# COMMUNICATION.net
KiCad netlist of a schematic drawn in Altium Designer
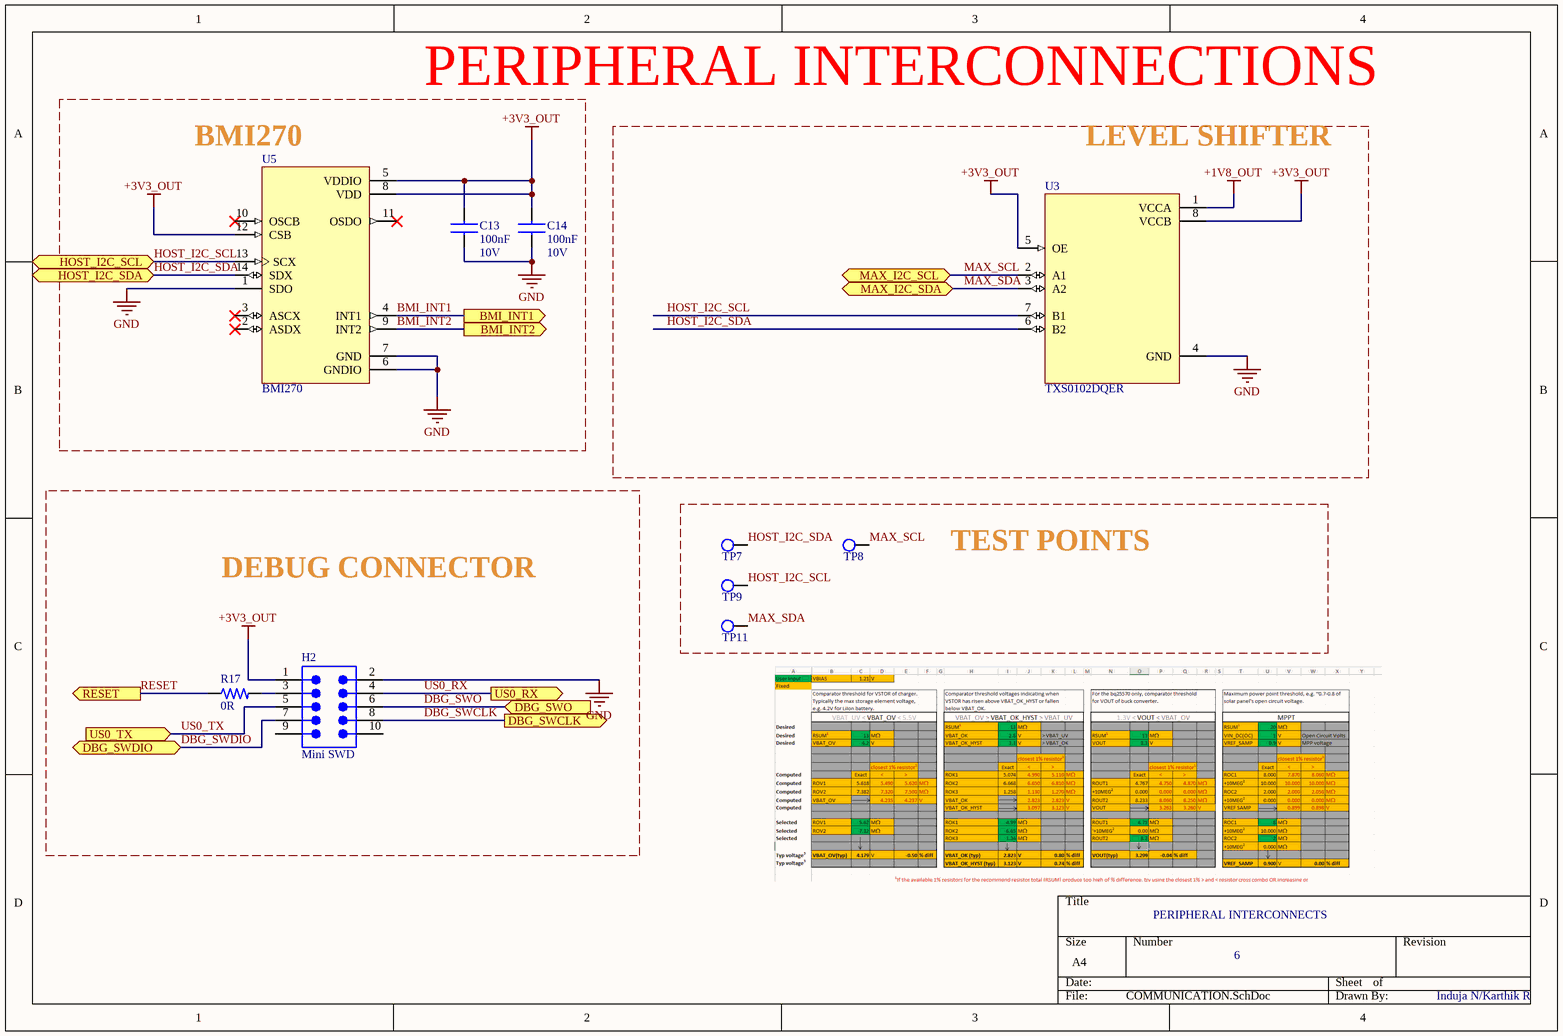
[diagram p0: COMMUNICATION.SchDoc]

(export (version "E")
  (design (tool "Eeschema 10.0.6"))
  (components
    (comp (ref "C13")
      (value "100nF")
      (footprint "CAP_0603_1MM")
      (description "0603 0.1 uF 10 V ±10% Tolerance X7R SMT Multilayer Ceramic Chip Capacitor")
      (fields
        (field (name "MANUFACTURER") "Vishay")
        (field (name "MANUFACTURER PART NUMBER") "VJ0603Y104KXQCW1BC")
        (field (name "VOLTAGE RATING (DC)") "10V")
      )
      (libsource (lib "LPEDT_Components") (part "CAP 0.1uF 0603"))
    )
    (comp (ref "C14")
      (value "100nF")
      (footprint "CAP_0603_1MM")
      (description "0603 0.1 uF 10 V ±10% Tolerance X7R SMT Multilayer Ceramic Chip Capacitor")
      (fields
        (field (name "MANUFACTURER") "Vishay")
        (field (name "MANUFACTURER PART NUMBER") "VJ0603Y104KXQCW1BC")
        (field (name "VOLTAGE RATING (DC)") "10V")
      )
      (libsource (lib "LPEDT_Components") (part "CAP 0.1uF 0603"))
    )
    (comp (ref "H2")
      (value "Mini SWD")
      (footprint "FTSH-105-01-XXX-DV-K")
      (description "Mini SWD 0.05\" Pitch Connector - 10 Pin SMT Box Header")
      (fields
        (field (name "MANUFACTURER") "Adafruit Industries")
        (field (name "MANUFACTURER PART NUMBER") "4048")
      )
      (libsource (lib "LPEDT_Components") (part "Debug Connector Mini SWD - 0.05{dblquote}"))
    )
    (comp (ref "R17")
      (value "0R")
      (footprint "RES_0603_1608X06")
      (description "GENERAL PURPOSE CHIP RESISTOR Metal Glaze/thick Film, 0.1W, 0ohm, Surface Mount, 0603")
      (fields
        (field (name "MANUFACTURER") "Yageo Group")
        (field (name "MANUFACTURER PART NUMBER") "RC0603JR-070RL")
      )
      (libsource (lib "LPEDT_Components") (part "RES 0R 0603"))
    )
    (comp (ref "TP7")
      (value "Test Point")
      (footprint "Test Point")
      (libsource (lib "LPEDT_Components") (part "Test Point"))
    )
    (comp (ref "TP8")
      (value "Test Point")
      (footprint "Test Point")
      (libsource (lib "LPEDT_Components") (part "Test Point"))
    )
    (comp (ref "TP9")
      (value "Test Point")
      (footprint "Test Point")
      (libsource (lib "LPEDT_Components") (part "Test Point"))
    )
    (comp (ref "TP11")
      (value "Test Point")
      (footprint "Test Point")
      (libsource (lib "LPEDT_Components") (part "Test Point"))
    )
    (comp (ref "U3")
      (value "TXS0102DQER")
      (footprint "SON35P140X100X40-8N")
      (description "2-Bit Bidirectional Voltage-Level Shifter for Open-Drain and Push-Pull Application")
      (fields (field (name "MF") "Texas Instruments"))
      (libsource (lib "LPEDT_Components") (part "TXS0102DQER"))
    )
    (comp (ref "U5")
      (value "BMI270")
      (footprint "XDCR_BMI270")
      (description "Accelerometer, Gyroscope, 6 Axis Sensor IÂ²C, SPI Output")
      (fields (field (name "DIGI-KEY_PART_NUMBER") "828-1091-2-ND") (field (name "MF") "Bosch Sensortec"))
      (libsource (lib "LPEDT_Components") (part "BMI270"))
    )
  )
  (nets
    (net (code "1") (name "+1V8_OUT") (class "Default")
      (node (ref "U3") (pin "1") (pinfunction "VCCA_1") (pintype "power_in"))
    )
    (net (code "2") (name "+3V3_OUT") (class "Default")
      (node (ref "C13") (pin "1") (pinfunction "1_1") (pintype "passive"))
      (node (ref "C14") (pin "1") (pinfunction "1_1") (pintype "passive"))
      (node (ref "H2") (pin "1") (pinfunction "1_1") (pintype "passive"))
      (node (ref "U3") (pin "5") (pinfunction "OE_5") (pintype "input"))
      (node (ref "U3") (pin "8") (pinfunction "VCCB_8") (pintype "power_in"))
      (node (ref "U5") (pin "12") (pinfunction "CSB_12") (pintype "input"))
      (node (ref "U5") (pin "5") (pinfunction "VDDIO_5") (pintype "power_in"))
      (node (ref "U5") (pin "8") (pinfunction "VDD_8") (pintype "power_in"))
    )
    (net (code "3") (name "/BMI_INT1") (class "Default")
      (node (ref "U5") (pin "4") (pinfunction "INT1_4") (pintype "output"))
    )
    (net (code "4") (name "/BMI_INT2") (class "Default")
      (node (ref "U5") (pin "9") (pinfunction "INT2_9") (pintype "output"))
    )
    (net (code "5") (name "/DBG_SWCLK") (class "Default")
      (node (ref "H2") (pin "8") (pinfunction "8_8") (pintype "passive"))
    )
    (net (code "6") (name "/DBG_SWDIO") (class "Default")
      (node (ref "H2") (pin "7") (pinfunction "7_7") (pintype "passive"))
    )
    (net (code "7") (name "/DBG_SWO") (class "Default")
      (node (ref "H2") (pin "6") (pinfunction "6_6") (pintype "passive"))
    )
    (net (code "8") (name "/HOST_I2C_SCL") (class "Default")
      (node (ref "TP9") (pin "1") (pinfunction "1_1") (pintype "passive"))
      (node (ref "U3") (pin "7") (pinfunction "B1_7") (pintype "bidirectional"))
      (node (ref "U5") (pin "13") (pinfunction "SCX_13") (pintype "input"))
    )
    (net (code "9") (name "/HOST_I2C_SDA") (class "Default")
      (node (ref "TP7") (pin "1") (pinfunction "1_1") (pintype "passive"))
      (node (ref "U3") (pin "6") (pinfunction "B2_6") (pintype "bidirectional"))
      (node (ref "U5") (pin "14") (pinfunction "SDX_14") (pintype "bidirectional"))
    )
    (net (code "10") (name "/MAX_SCL") (class "Default")
      (node (ref "TP8") (pin "1") (pinfunction "1_1") (pintype "passive"))
      (node (ref "U3") (pin "2") (pinfunction "A1_2") (pintype "bidirectional"))
    )
    (net (code "11") (name "/MAX_SDA") (class "Default")
      (node (ref "TP11") (pin "1") (pinfunction "1_1") (pintype "passive"))
      (node (ref "U3") (pin "3") (pinfunction "A2_3") (pintype "bidirectional"))
    )
    (net (code "12") (name "/RESET") (class "Default")
      (node (ref "R17") (pin "1") (pinfunction "1_1") (pintype "passive"))
    )
    (net (code "13") (name "/US0_RX") (class "Default")
      (node (ref "H2") (pin "4") (pinfunction "4_4") (pintype "passive"))
    )
    (net (code "14") (name "/US0_TX") (class "Default")
      (node (ref "H2") (pin "5") (pinfunction "5_5") (pintype "passive"))
    )
    (net (code "15") (name "GND") (class "Default")
      (node (ref "C13") (pin "2") (pinfunction "2_2") (pintype "passive"))
      (node (ref "C14") (pin "2") (pinfunction "2_2") (pintype "passive"))
      (node (ref "H2") (pin "2") (pinfunction "2_2") (pintype "passive"))
      (node (ref "U3") (pin "4") (pinfunction "GND_4") (pintype "power_in"))
      (node (ref "U5") (pin "1") (pinfunction "SDO_1") (pintype "passive"))
      (node (ref "U5") (pin "6") (pinfunction "GNDIO_6") (pintype "power_in"))
      (node (ref "U5") (pin "7") (pinfunction "GND_7") (pintype "power_in"))
    )
    (net (code "16") (name "Net-(H2-Pad3)") (class "Default")
      (node (ref "H2") (pin "3") (pinfunction "3_3") (pintype "passive"))
      (node (ref "R17") (pin "2") (pinfunction "2_2") (pintype "passive"))
    )
    (net (code "17") (name "unconnected-(H2-Pad9)") (class "Default")
      (node (ref "H2") (pin "9") (pinfunction "9_9") (pintype "passive"))
    )
    (net (code "18") (name "unconnected-(H2-Pad10)") (class "Default")
      (node (ref "H2") (pin "10") (pinfunction "10_10") (pintype "passive"))
    )
    (net (code "19") (name "unconnected-(U5-ASCX-Pad3)") (class "Default")
      (node (ref "U5") (pin "3") (pinfunction "ASCX_3") (pintype "bidirectional+no_connect"))
    )
    (net (code "20") (name "unconnected-(U5-ASDX-Pad2)") (class "Default")
      (node (ref "U5") (pin "2") (pinfunction "ASDX_2") (pintype "bidirectional+no_connect"))
    )
    (net (code "21") (name "unconnected-(U5-OSCB-Pad10)") (class "Default")
      (node (ref "U5") (pin "10") (pinfunction "OSCB_10") (pintype "input+no_connect"))
    )
    (net (code "22") (name "unconnected-(U5-OSDO-Pad11)") (class "Default")
      (node (ref "U5") (pin "11") (pinfunction "OSDO_11") (pintype "output+no_connect"))
    )
  )
)
